# lra_block.net
KiCad netlist of a schematic drawn in Altium Designer
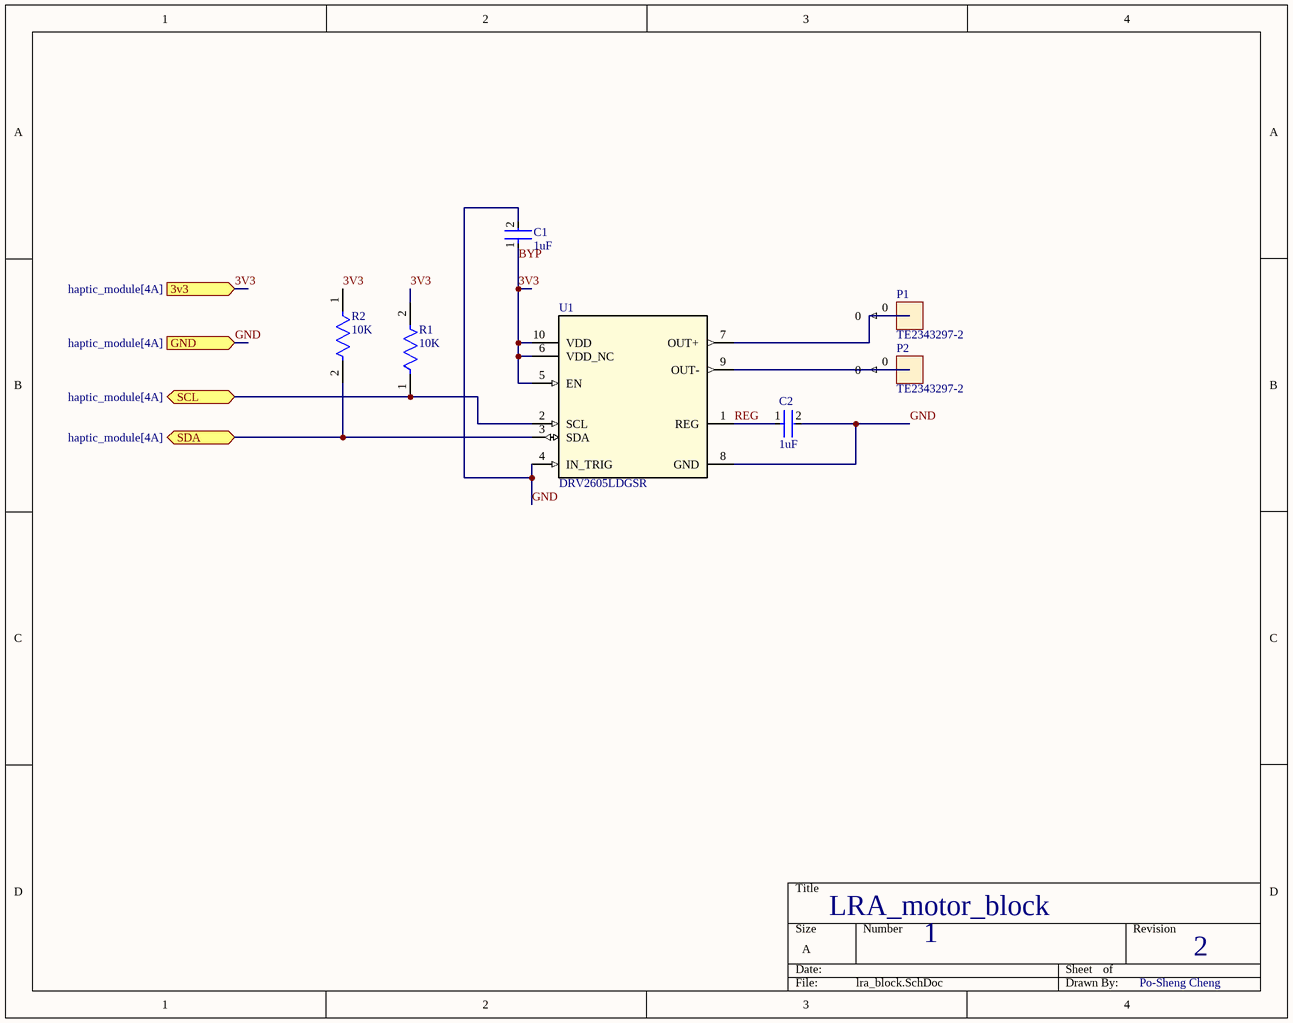
[diagram p0: lra_block.SchDoc]

(export (version "E")
  (design (tool "Eeschema 10.0.6"))
  (components
    (comp (ref "C1")
      (value "1uF")
      (footprint "FP-CC0805-0_85-MFG")
      (description "CAP CER 1UF 16V X7R 0805")
      (fields
        (field (name "MANUFACTURER") "Yageo")
        (field (name "OCTOPART") "https://octopart.com/cc0805kkx7r7bb105-yageo-8376555")
      )
      (libsource (lib "Altium Content Vault") (part "11868f565c42a9108669ba33697ecf6"))
    )
    (comp (ref "C2")
      (value "1uF")
      (footprint "FP-CC0805-0_85-MFG")
      (description "CAP CER 1UF 16V X7R 0805")
      (fields
        (field (name "MANUFACTURER") "Yageo")
        (field (name "OCTOPART") "https://octopart.com/cc0805kkx7r7bb105-yageo-8376555")
      )
      (libsource (lib "Altium Content Vault") (part "11868f565c42a9108669ba33697ecf6"))
    )
    (comp (ref "P1")
      (value "TE2343297-2")
      (footprint "TE2343297-2")
      (libsource (lib "TE2343297-2") (part "TE2343297-2"))
    )
    (comp (ref "P2")
      (value "TE2343297-2")
      (footprint "TE2343297-2")
      (libsource (lib "TE2343297-2") (part "TE2343297-2"))
    )
    (comp (ref "R1")
      (value "10K")
      (footprint "FP-RT0603-MFG")
      (description "RES SMD 10K OHM 0.1% 1/10W 0603")
      (fields
        (field (name "TOLERANCE") "0.001")
        (field (name "OCTOPART") "https://octopart.com/rt0603bre0710kl-yageo-1273959")
      )
      (libsource (lib "Altium Content Vault") (part "1029c3af85768c4190bb7ad29bc67b5"))
    )
    (comp (ref "R2")
      (value "10K")
      (footprint "FP-RT0603-MFG")
      (description "RES SMD 10K OHM 0.1% 1/10W 0603")
      (fields
        (field (name "TOLERANCE") "0.001")
        (field (name "OCTOPART") "https://octopart.com/rt0603bre0710kl-yageo-1273959")
      )
      (libsource (lib "Altium Content Vault") (part "1029c3af85768c4190bb7ad29bc67b5"))
    )
    (comp (ref "U1")
      (value "DRV2605LDGSR")
      (footprint "DGS0010A")
      (description "No Description Available")
      (fields (field (name "PARTNUMBER") "DRV2605LDGS") (field (name "MANUFACTURER") "Texas Instruments"))
      (libsource (lib "DRV2605LDGSR") (part "DRV2605LDGSR"))
    )
  )
  (nets
    (net (code "1") (name "/3V3") (class "Default")
      (node (ref "C1") (pin "1") (pinfunction "1_1") (pintype "passive"))
      (node (ref "R1") (pin "2") (pinfunction "2_2") (pintype "passive"))
      (node (ref "R2") (pin "1") (pinfunction "1_1") (pintype "passive"))
      (node (ref "U1") (pin "10") (pinfunction "VDD_10") (pintype "power_in"))
      (node (ref "U1") (pin "5") (pinfunction "EN_5") (pintype "input"))
      (node (ref "U1") (pin "6") (pinfunction "VDD_NC_6") (pintype "power_in"))
    )
    (net (code "2") (name "/GND") (class "Default")
      (node (ref "C1") (pin "2") (pinfunction "2_2") (pintype "passive"))
      (node (ref "C2") (pin "2") (pinfunction "2_2") (pintype "passive"))
      (node (ref "U1") (pin "4") (pinfunction "IN_TRIG_4") (pintype "input"))
      (node (ref "U1") (pin "8") (pinfunction "GND_8") (pintype "power_in"))
    )
    (net (code "3") (name "/REG") (class "Default")
      (node (ref "C2") (pin "1") (pinfunction "1_1") (pintype "passive"))
      (node (ref "U1") (pin "1") (pinfunction "REG_1") (pintype "power_in"))
    )
    (net (code "4") (name "/SCL") (class "Default")
      (node (ref "R1") (pin "1") (pinfunction "1_1") (pintype "passive"))
      (node (ref "U1") (pin "2") (pinfunction "SCL_2") (pintype "input"))
    )
    (net (code "5") (name "/SDA") (class "Default")
      (node (ref "R2") (pin "2") (pinfunction "2_2") (pintype "passive"))
      (node (ref "U1") (pin "3") (pinfunction "SDA_3") (pintype "bidirectional"))
    )
    (net (code "6") (name "Net-(U1-OUT+)") (class "Default")
      (node (ref "P1") (pin "0") (pinfunction "0_0") (pintype "input"))
      (node (ref "U1") (pin "7") (pinfunction "OUT+_7") (pintype "output"))
    )
    (net (code "7") (name "Net-(U1-OUT-)") (class "Default")
      (node (ref "P2") (pin "0") (pinfunction "0_0") (pintype "input"))
      (node (ref "U1") (pin "9") (pinfunction "OUT-_9") (pintype "output"))
    )
  )
)
